# EnvironmentOnAStick.net
KiCad netlist of a schematic drawn in EAGLE
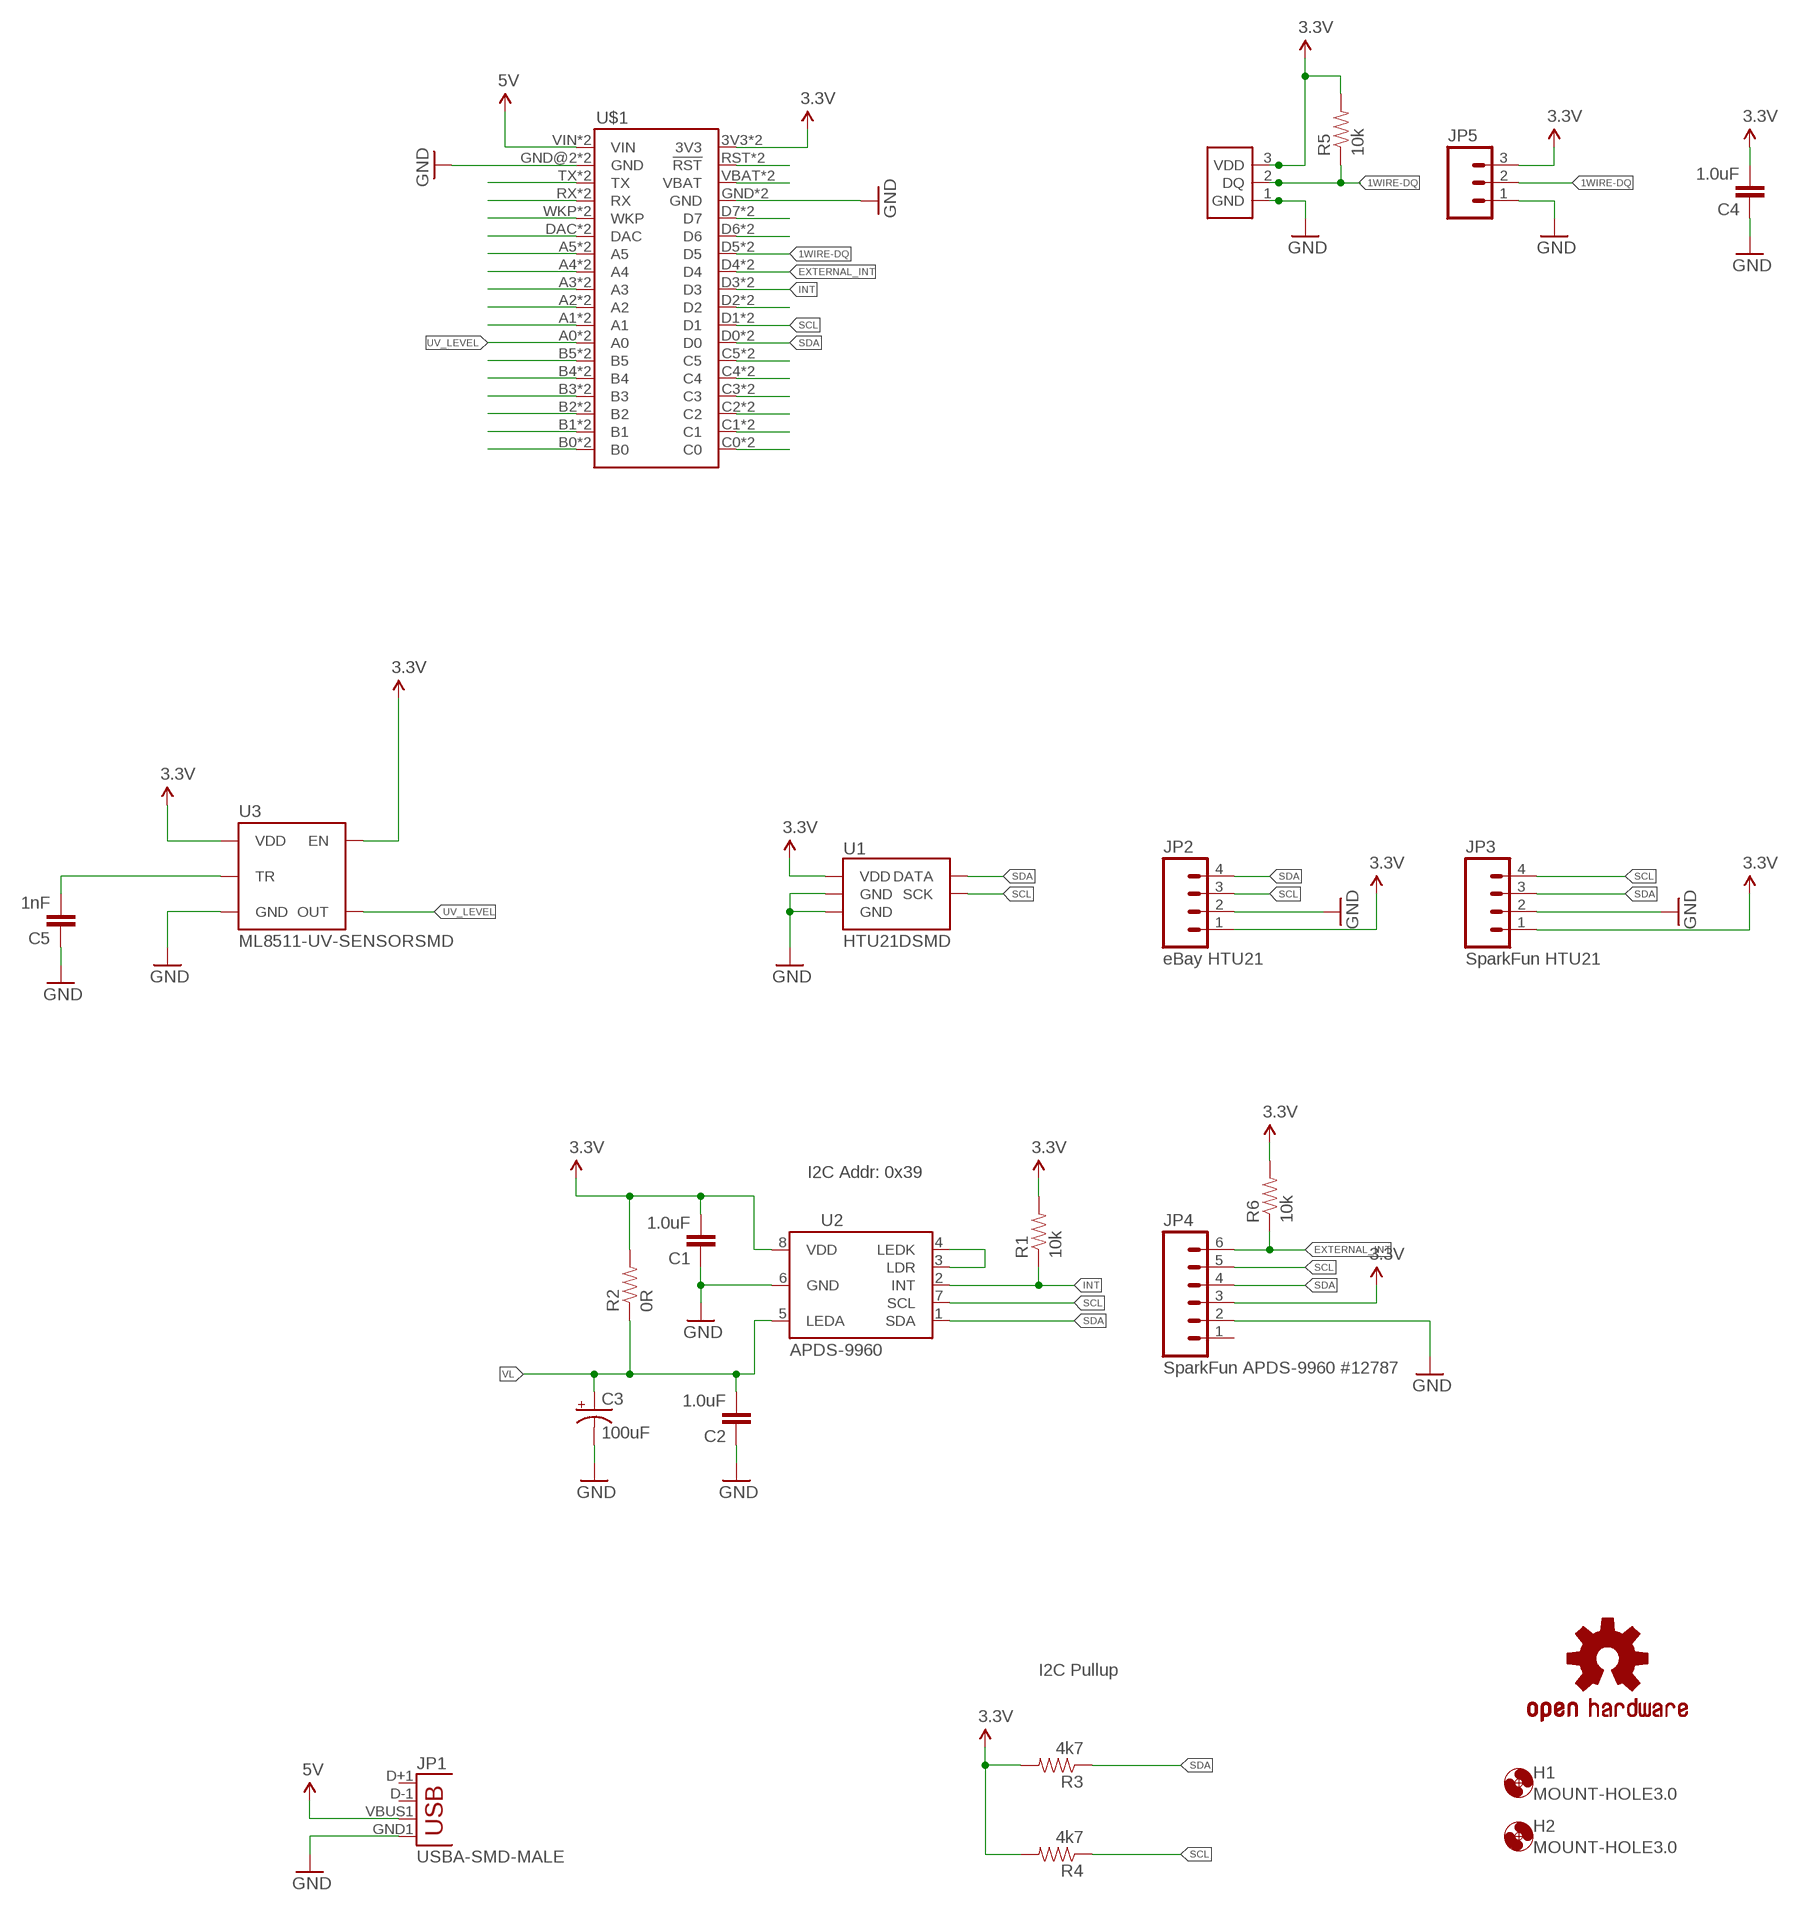
[diagram p0: schematic, sheet 1]

(export (version "E")
  (design (tool "Eeschema 10.0.6"))
  (components
    (comp (ref "C1")
      (value "1.0uF")
      (footprint "eagle-import:0805-CAP")
      (libsource (lib "eagle-import") (part "1.0UF-25V-+80/-20(0805){dblquote}"))
    )
    (comp (ref "C2")
      (value "1.0uF")
      (footprint "eagle-import:0805-CAP")
      (libsource (lib "eagle-import") (part "1.0UF-25V-+80/-20(0805){dblquote}"))
    )
    (comp (ref "C3")
      (value "100uF")
      (footprint "eagle-import:EIA7343")
      (libsource (lib "eagle-import") (part "100UF-10V-10%(TANT)"))
    )
    (comp (ref "C4")
      (value "1.0uF")
      (footprint "eagle-import:0805-CAP")
      (libsource (lib "eagle-import") (part "1.0UF-25V-+80/-20(0805){dblquote}"))
    )
    (comp (ref "C5")
      (value "1nF")
      (footprint "eagle-import:0805-CAP")
      (libsource (lib "eagle-import") (part "1.0UF-25V-+80/-20(0805){dblquote}"))
    )
    (comp (ref "H1")
      (value "MOUNT-HOLE3.0")
      (footprint "eagle-import:3,0")
      (libsource (lib "eagle-import") (part "MOUNT-HOLE3.0"))
    )
    (comp (ref "H2")
      (value "MOUNT-HOLE3.0")
      (footprint "eagle-import:3,0")
      (libsource (lib "eagle-import") (part "MOUNT-HOLE3.0"))
    )
    (comp (ref "JP1")
      (value "USBA-SMD-MALE")
      (footprint "eagle-import:USB-A-SMT-MALE")
      (libsource (lib "eagle-import") (part "USBA-SMD-MALE"))
    )
    (comp (ref "JP2")
      (value "eBay HTU21")
      (footprint "eagle-import:1X04")
      (libsource (lib "eagle-import") (part "M04PTH"))
    )
    (comp (ref "JP3")
      (value "SparkFun HTU21")
      (footprint "eagle-import:1X04")
      (libsource (lib "eagle-import") (part "M04PTH"))
    )
    (comp (ref "JP4")
      (value "SparkFun APDS-9960 #12787")
      (footprint "eagle-import:1X06")
      (libsource (lib "eagle-import") (part "M06SILK_FEMALE_PTH"))
    )
    (comp (ref "JP5")
      (value "M03POLAR")
      (footprint "eagle-import:MOLEX-1X3")
      (libsource (lib "eagle-import") (part "M03POLAR"))
    )
    (comp (ref "LOGO1")
      (value "OSHW-LOGOM")
      (footprint "eagle-import:OSHW-LOGO-M")
      (libsource (lib "eagle-import") (part "OSHW-LOGOM"))
    )
    (comp (ref "R1")
      (value "10k")
      (footprint "eagle-import:0805")
      (libsource (lib "eagle-import") (part "RESISTOR0805-RES"))
    )
    (comp (ref "R2")
      (value "0R")
      (footprint "eagle-import:0805")
      (libsource (lib "eagle-import") (part "RESISTOR0805-RES"))
    )
    (comp (ref "R3")
      (value "4k7")
      (footprint "eagle-import:0805")
      (libsource (lib "eagle-import") (part "RESISTOR0805-RES"))
    )
    (comp (ref "R4")
      (value "4k7")
      (footprint "eagle-import:0805")
      (libsource (lib "eagle-import") (part "RESISTOR0805-RES"))
    )
    (comp (ref "R5")
      (value "10k")
      (footprint "eagle-import:0805")
      (libsource (lib "eagle-import") (part "RESISTOR0805-RES"))
    )
    (comp (ref "R6")
      (value "10k")
      (footprint "eagle-import:0805")
      (libsource (lib "eagle-import") (part "RESISTOR0805-RES"))
    )
    (comp (ref "S1")
      (value "SENSOR-DS18B20")
      (footprint "eagle-import:TO-92-TRIANGLE")
      (libsource (lib "eagle-import") (part "SENSOR-DS18B20"))
    )
    (comp (ref "U$1")
      (value "ELECTRONDUALNAMED")
      (footprint "eagle-import:ELECTRON_SIMPLE_SILK_NAMES_DUAL")
      (libsource (lib "eagle-import") (part "ELECTRONDUALNAMED"))
    )
    (comp (ref "U1")
      (value "HTU21DSMD")
      (footprint "eagle-import:HTU21D")
      (libsource (lib "eagle-import") (part "HTU21DSMD"))
    )
    (comp (ref "U2")
      (value "APDS-9960")
      (footprint "eagle-import:APDS-9960")
      (libsource (lib "eagle-import") (part "APDS-9960"))
    )
    (comp (ref "U3")
      (value "ML8511-UV-SENSORSMD")
      (footprint "eagle-import:ML8511")
      (libsource (lib "eagle-import") (part "ML8511-UV-SENSORSMD"))
    )
  )
  (nets
    (net (code "1") (name "1WIRE-DQ") (class "Default")
      (node (ref "JP5") (pin "2") (pinfunction "2_2") (pintype "passive"))
      (node (ref "R5") (pin "1") (pinfunction "1_1") (pintype "passive"))
      (node (ref "S1") (pin "2") (pinfunction "DQ_2") (pintype "bidirectional"))
      (node (ref "U$1") (pin "D5") (pinfunction "D5_D5") (pintype "bidirectional"))
      (node (ref "U$1") (pin "D5_1") (pinfunction "D5_D5_1") (pintype "bidirectional"))
    )
    (net (code "2") (name "3.3V") (class "Default")
      (node (ref "C1") (pin "2") (pinfunction "2_2") (pintype "passive"))
      (node (ref "C4") (pin "2") (pinfunction "2_2") (pintype "passive"))
      (node (ref "JP2") (pin "1") (pinfunction "1_1") (pintype "passive"))
      (node (ref "JP3") (pin "1") (pinfunction "1_1") (pintype "passive"))
      (node (ref "JP4") (pin "3") (pinfunction "3_3") (pintype "passive"))
      (node (ref "JP5") (pin "3") (pinfunction "3_3") (pintype "passive"))
      (node (ref "R1") (pin "2") (pinfunction "2_2") (pintype "passive"))
      (node (ref "R2") (pin "2") (pinfunction "2_2") (pintype "passive"))
      (node (ref "R3") (pin "2") (pinfunction "2_2") (pintype "passive"))
      (node (ref "R4") (pin "2") (pinfunction "2_2") (pintype "passive"))
      (node (ref "R5") (pin "2") (pinfunction "2_2") (pintype "passive"))
      (node (ref "R6") (pin "2") (pinfunction "2_2") (pintype "passive"))
      (node (ref "S1") (pin "3") (pinfunction "VDD_3") (pintype "bidirectional"))
      (node (ref "U$1") (pin "3V3") (pinfunction "3V3_3V3") (pintype "power_in"))
      (node (ref "U$1") (pin "3V3_1") (pinfunction "3V3_3V3_1") (pintype "power_in"))
      (node (ref "U1") (pin "VDD") (pinfunction "VDD_VDD") (pintype "power_in"))
      (node (ref "U2") (pin "8") (pinfunction "VDD_8") (pintype "bidirectional"))
      (node (ref "U3") (pin "4") (pinfunction "EN_4") (pintype "input"))
      (node (ref "U3") (pin "7") (pinfunction "VDD_7") (pintype "power_in"))
    )
    (net (code "3") (name "5V") (class "Default")
      (node (ref "JP1") (pin "VBUS1") (pinfunction "VBUS_VBUS1") (pintype "bidirectional"))
      (node (ref "U$1") (pin "VIN") (pinfunction "VIN_VIN") (pintype "power_in"))
      (node (ref "U$1") (pin "VIN_1B") (pinfunction "VIN_VIN_1B") (pintype "power_in"))
    )
    (net (code "4") (name "EXTERNAL_INT") (class "Default")
      (node (ref "JP4") (pin "6") (pinfunction "6_6") (pintype "passive"))
      (node (ref "R6") (pin "1") (pinfunction "1_1") (pintype "passive"))
      (node (ref "U$1") (pin "D4") (pinfunction "D4_D4") (pintype "bidirectional"))
      (node (ref "U$1") (pin "D4_1") (pinfunction "D4_D4_1") (pintype "bidirectional"))
    )
    (net (code "5") (name "GND") (class "Default")
      (node (ref "C1") (pin "1") (pinfunction "1_1") (pintype "passive"))
      (node (ref "C2") (pin "1") (pinfunction "1_1") (pintype "passive"))
      (node (ref "C3") (pin "C") (pinfunction "-_C") (pintype "passive"))
      (node (ref "C4") (pin "1") (pinfunction "1_1") (pintype "passive"))
      (node (ref "C5") (pin "1") (pinfunction "1_1") (pintype "passive"))
      (node (ref "JP1") (pin "GND1") (pinfunction "GND_GND1") (pintype "bidirectional"))
      (node (ref "JP2") (pin "2") (pinfunction "2_2") (pintype "passive"))
      (node (ref "JP3") (pin "2") (pinfunction "2_2") (pintype "passive"))
      (node (ref "JP4") (pin "2") (pinfunction "2_2") (pintype "passive"))
      (node (ref "JP5") (pin "1") (pinfunction "1_1") (pintype "passive"))
      (node (ref "S1") (pin "1") (pinfunction "GND_1") (pintype "bidirectional"))
      (node (ref "U$1") (pin "GND") (pinfunction "GND_GND") (pintype "power_in"))
      (node (ref "U$1") (pin "GND@2") (pinfunction "GND_GND@2") (pintype "power_in"))
      (node (ref "U$1") (pin "GND_1") (pinfunction "GND_GND_1") (pintype "power_in"))
      (node (ref "U$1") (pin "GND_1B") (pinfunction "GND_GND_1B") (pintype "power_in"))
      (node (ref "U1") (pin "7") (pinfunction "GND_7") (pintype "power_in"))
      (node (ref "U1") (pin "GND") (pinfunction "GND_GND") (pintype "power_in"))
      (node (ref "U2") (pin "6") (pinfunction "GND_6") (pintype "bidirectional"))
      (node (ref "U3") (pin "5") (pinfunction "GND_5") (pintype "power_in"))
    )
    (net (code "6") (name "INT") (class "Default")
      (node (ref "R1") (pin "1") (pinfunction "1_1") (pintype "passive"))
      (node (ref "U$1") (pin "D3") (pinfunction "D3_D3") (pintype "bidirectional"))
      (node (ref "U$1") (pin "D3_1") (pinfunction "D3_D3_1") (pintype "bidirectional"))
      (node (ref "U2") (pin "2") (pinfunction "INT_2") (pintype "bidirectional"))
    )
    (net (code "7") (name "Net-(U$1-A1-PadA1_1)") (class "Default")
      (node (ref "U$1") (pin "A1") (pinfunction "A1_A1") (pintype "bidirectional"))
      (node (ref "U$1") (pin "A1_1") (pinfunction "A1_A1_1") (pintype "bidirectional"))
    )
    (net (code "8") (name "Net-(U$1-A2-PadA2_1)") (class "Default")
      (node (ref "U$1") (pin "A2") (pinfunction "A2_A2") (pintype "bidirectional"))
      (node (ref "U$1") (pin "A2_1") (pinfunction "A2_A2_1") (pintype "bidirectional"))
    )
    (net (code "9") (name "Net-(U$1-A3-PadA3_1)") (class "Default")
      (node (ref "U$1") (pin "A3") (pinfunction "A3_A3") (pintype "bidirectional"))
      (node (ref "U$1") (pin "A3_1") (pinfunction "A3_A3_1") (pintype "bidirectional"))
    )
    (net (code "10") (name "Net-(U$1-A4-PadA4_1)") (class "Default")
      (node (ref "U$1") (pin "A4") (pinfunction "A4_A4") (pintype "bidirectional"))
      (node (ref "U$1") (pin "A4_1") (pinfunction "A4_A4_1") (pintype "bidirectional"))
    )
    (net (code "11") (name "Net-(U$1-A5-PadA5_1)") (class "Default")
      (node (ref "U$1") (pin "A5") (pinfunction "A5_A5") (pintype "bidirectional"))
      (node (ref "U$1") (pin "A5_1") (pinfunction "A5_A5_1") (pintype "bidirectional"))
    )
    (net (code "12") (name "Net-(U$1-B0-PadB0_1)") (class "Default")
      (node (ref "U$1") (pin "B0") (pinfunction "B0_B0") (pintype "bidirectional"))
      (node (ref "U$1") (pin "B0_1") (pinfunction "B0_B0_1") (pintype "bidirectional"))
    )
    (net (code "13") (name "Net-(U$1-B1-PadB1_1)") (class "Default")
      (node (ref "U$1") (pin "B1") (pinfunction "B1_B1") (pintype "bidirectional"))
      (node (ref "U$1") (pin "B1_1") (pinfunction "B1_B1_1") (pintype "bidirectional"))
    )
    (net (code "14") (name "Net-(U$1-B2-PadB2_1)") (class "Default")
      (node (ref "U$1") (pin "B2") (pinfunction "B2_B2") (pintype "bidirectional"))
      (node (ref "U$1") (pin "B2_1") (pinfunction "B2_B2_1") (pintype "bidirectional"))
    )
    (net (code "15") (name "Net-(U$1-B3-PadB3_1)") (class "Default")
      (node (ref "U$1") (pin "B3") (pinfunction "B3_B3") (pintype "bidirectional"))
      (node (ref "U$1") (pin "B3_1") (pinfunction "B3_B3_1") (pintype "bidirectional"))
    )
    (net (code "16") (name "Net-(U$1-B4-PadB4_1)") (class "Default")
      (node (ref "U$1") (pin "B4") (pinfunction "B4_B4") (pintype "bidirectional"))
      (node (ref "U$1") (pin "B4_1") (pinfunction "B4_B4_1") (pintype "bidirectional"))
    )
    (net (code "17") (name "Net-(U$1-B5-PadB5_1)") (class "Default")
      (node (ref "U$1") (pin "B5") (pinfunction "B5_B5") (pintype "bidirectional"))
      (node (ref "U$1") (pin "B5_1") (pinfunction "B5_B5_1") (pintype "bidirectional"))
    )
    (net (code "18") (name "Net-(U$1-C0-PadC0_1)") (class "Default")
      (node (ref "U$1") (pin "C0") (pinfunction "C0_C0") (pintype "bidirectional"))
      (node (ref "U$1") (pin "C0_1") (pinfunction "C0_C0_1") (pintype "bidirectional"))
    )
    (net (code "19") (name "Net-(U$1-C1-PadC1_1)") (class "Default")
      (node (ref "U$1") (pin "C1") (pinfunction "C1_C1") (pintype "bidirectional"))
      (node (ref "U$1") (pin "C1_1") (pinfunction "C1_C1_1") (pintype "bidirectional"))
    )
    (net (code "20") (name "Net-(U$1-C2-PadC2_1)") (class "Default")
      (node (ref "U$1") (pin "C2") (pinfunction "C2_C2") (pintype "bidirectional"))
      (node (ref "U$1") (pin "C2_1") (pinfunction "C2_C2_1") (pintype "bidirectional"))
    )
    (net (code "21") (name "Net-(U$1-C3-PadC3_1)") (class "Default")
      (node (ref "U$1") (pin "C3") (pinfunction "C3_C3") (pintype "bidirectional"))
      (node (ref "U$1") (pin "C3_1") (pinfunction "C3_C3_1") (pintype "bidirectional"))
    )
    (net (code "22") (name "Net-(U$1-C4-PadC4_1)") (class "Default")
      (node (ref "U$1") (pin "C4") (pinfunction "C4_C4") (pintype "bidirectional"))
      (node (ref "U$1") (pin "C4_1") (pinfunction "C4_C4_1") (pintype "bidirectional"))
    )
    (net (code "23") (name "Net-(U$1-C5-PadC5_1)") (class "Default")
      (node (ref "U$1") (pin "C5") (pinfunction "C5_C5") (pintype "bidirectional"))
      (node (ref "U$1") (pin "C5_1") (pinfunction "C5_C5_1") (pintype "bidirectional"))
    )
    (net (code "24") (name "Net-(U$1-D2-PadD2_1)") (class "Default")
      (node (ref "U$1") (pin "D2") (pinfunction "D2_D2") (pintype "bidirectional"))
      (node (ref "U$1") (pin "D2_1") (pinfunction "D2_D2_1") (pintype "bidirectional"))
    )
    (net (code "25") (name "Net-(U$1-D6-PadD6_1)") (class "Default")
      (node (ref "U$1") (pin "D6") (pinfunction "D6_D6") (pintype "bidirectional"))
      (node (ref "U$1") (pin "D6_1") (pinfunction "D6_D6_1") (pintype "bidirectional"))
    )
    (net (code "26") (name "Net-(U$1-D7-PadD7_1)") (class "Default")
      (node (ref "U$1") (pin "D7") (pinfunction "D7_D7") (pintype "bidirectional"))
      (node (ref "U$1") (pin "D7_1") (pinfunction "D7_D7_1") (pintype "bidirectional"))
    )
    (net (code "27") (name "Net-(U$1-DAC-PadDAC_1)") (class "Default")
      (node (ref "U$1") (pin "DAC") (pinfunction "DAC_DAC") (pintype "bidirectional"))
      (node (ref "U$1") (pin "DAC_1") (pinfunction "DAC_DAC_1") (pintype "bidirectional"))
    )
    (net (code "28") (name "Net-(U$1-PadRX)") (class "Default")
      (node (ref "U$1") (pin "RX") (pinfunction "RX_RX") (pintype "bidirectional"))
      (node (ref "U$1") (pin "RX_1") (pinfunction "RX_RX_1") (pintype "bidirectional"))
    )
    (net (code "29") (name "Net-(U$1-PadTX)") (class "Default")
      (node (ref "U$1") (pin "TX") (pinfunction "TX_TX") (pintype "bidirectional"))
      (node (ref "U$1") (pin "TX_1") (pinfunction "TX_TX_1") (pintype "bidirectional"))
    )
    (net (code "30") (name "Net-(U$1-PadVBAT)") (class "Default")
      (node (ref "U$1") (pin "VBAT") (pinfunction "VBAT_VBAT") (pintype "passive"))
      (node (ref "U$1") (pin "VBATT_1") (pinfunction "VBAT_VBATT_1") (pintype "passive"))
    )
    (net (code "31") (name "Net-(U$1-PadWKP)") (class "Default")
      (node (ref "U$1") (pin "WKP") (pinfunction "WKP_WKP") (pintype "bidirectional"))
      (node (ref "U$1") (pin "WKP_1") (pinfunction "WKP_WKP_1") (pintype "bidirectional"))
    )
    (net (code "32") (name "Net-(U$1-~{RST}-PadRST)") (class "Default")
      (node (ref "U$1") (pin "RST") (pinfunction "~{RST}_RST") (pintype "bidirectional"))
      (node (ref "U$1") (pin "RST_1") (pinfunction "~{RST}_RST_1") (pintype "bidirectional"))
    )
    (net (code "33") (name "Net-(U2-LDR)") (class "Default")
      (node (ref "U2") (pin "3") (pinfunction "LDR_3") (pintype "bidirectional"))
      (node (ref "U2") (pin "4") (pinfunction "LEDK_4") (pintype "bidirectional"))
    )
    (net (code "34") (name "Net-(U3-TR)") (class "Default")
      (node (ref "C5") (pin "2") (pinfunction "2_2") (pintype "passive"))
      (node (ref "U3") (pin "10") (pinfunction "TR_10") (pintype "power_in"))
    )
    (net (code "35") (name "SCL") (class "Default")
      (node (ref "JP2") (pin "3") (pinfunction "3_3") (pintype "passive"))
      (node (ref "JP3") (pin "4") (pinfunction "4_4") (pintype "passive"))
      (node (ref "JP4") (pin "5") (pinfunction "5_5") (pintype "passive"))
      (node (ref "R4") (pin "1") (pinfunction "1_1") (pintype "passive"))
      (node (ref "U$1") (pin "D1") (pinfunction "D1_D1") (pintype "bidirectional"))
      (node (ref "U$1") (pin "D1_1") (pinfunction "D1_D1_1") (pintype "bidirectional"))
      (node (ref "U1") (pin "SCK") (pinfunction "SCK_SCK") (pintype "input"))
      (node (ref "U2") (pin "7") (pinfunction "SCL_7") (pintype "bidirectional"))
    )
    (net (code "36") (name "SDA") (class "Default")
      (node (ref "JP2") (pin "4") (pinfunction "4_4") (pintype "passive"))
      (node (ref "JP3") (pin "3") (pinfunction "3_3") (pintype "passive"))
      (node (ref "JP4") (pin "4") (pinfunction "4_4") (pintype "passive"))
      (node (ref "R3") (pin "1") (pinfunction "1_1") (pintype "passive"))
      (node (ref "U$1") (pin "D0") (pinfunction "D0_D0") (pintype "bidirectional"))
      (node (ref "U$1") (pin "D0_1") (pinfunction "D0_D0_1") (pintype "bidirectional"))
      (node (ref "U1") (pin "DATA") (pinfunction "DATA_DATA") (pintype "bidirectional"))
      (node (ref "U2") (pin "1") (pinfunction "SDA_1") (pintype "bidirectional"))
    )
    (net (code "37") (name "UV_LEVEL") (class "Default")
      (node (ref "U$1") (pin "A0") (pinfunction "A0_A0") (pintype "bidirectional"))
      (node (ref "U$1") (pin "A0_1") (pinfunction "A0_A0_1") (pintype "bidirectional"))
      (node (ref "U3") (pin "8") (pinfunction "OUT_8") (pintype "output"))
    )
    (net (code "38") (name "VL") (class "Default")
      (node (ref "C2") (pin "2") (pinfunction "2_2") (pintype "passive"))
      (node (ref "C3") (pin "A") (pinfunction "+_A") (pintype "passive"))
      (node (ref "R2") (pin "1") (pinfunction "1_1") (pintype "passive"))
      (node (ref "U2") (pin "5") (pinfunction "LEDA_5") (pintype "bidirectional"))
    )
    (net (code "39") (name "unconnected-(JP1-D+-PadD+1)") (class "Default")
      (node (ref "JP1") (pin "D+1") (pinfunction "D+_D+1") (pintype "bidirectional"))
    )
    (net (code "40") (name "unconnected-(JP1-D--PadD-1)") (class "Default")
      (node (ref "JP1") (pin "D-1") (pinfunction "D-_D-1") (pintype "bidirectional"))
    )
    (net (code "41") (name "unconnected-(JP4-Pad1)") (class "Default")
      (node (ref "JP4") (pin "1") (pinfunction "1_1") (pintype "passive"))
    )
  )
)
